# B198X.net
KiCad netlist of a schematic drawn in EAGLE
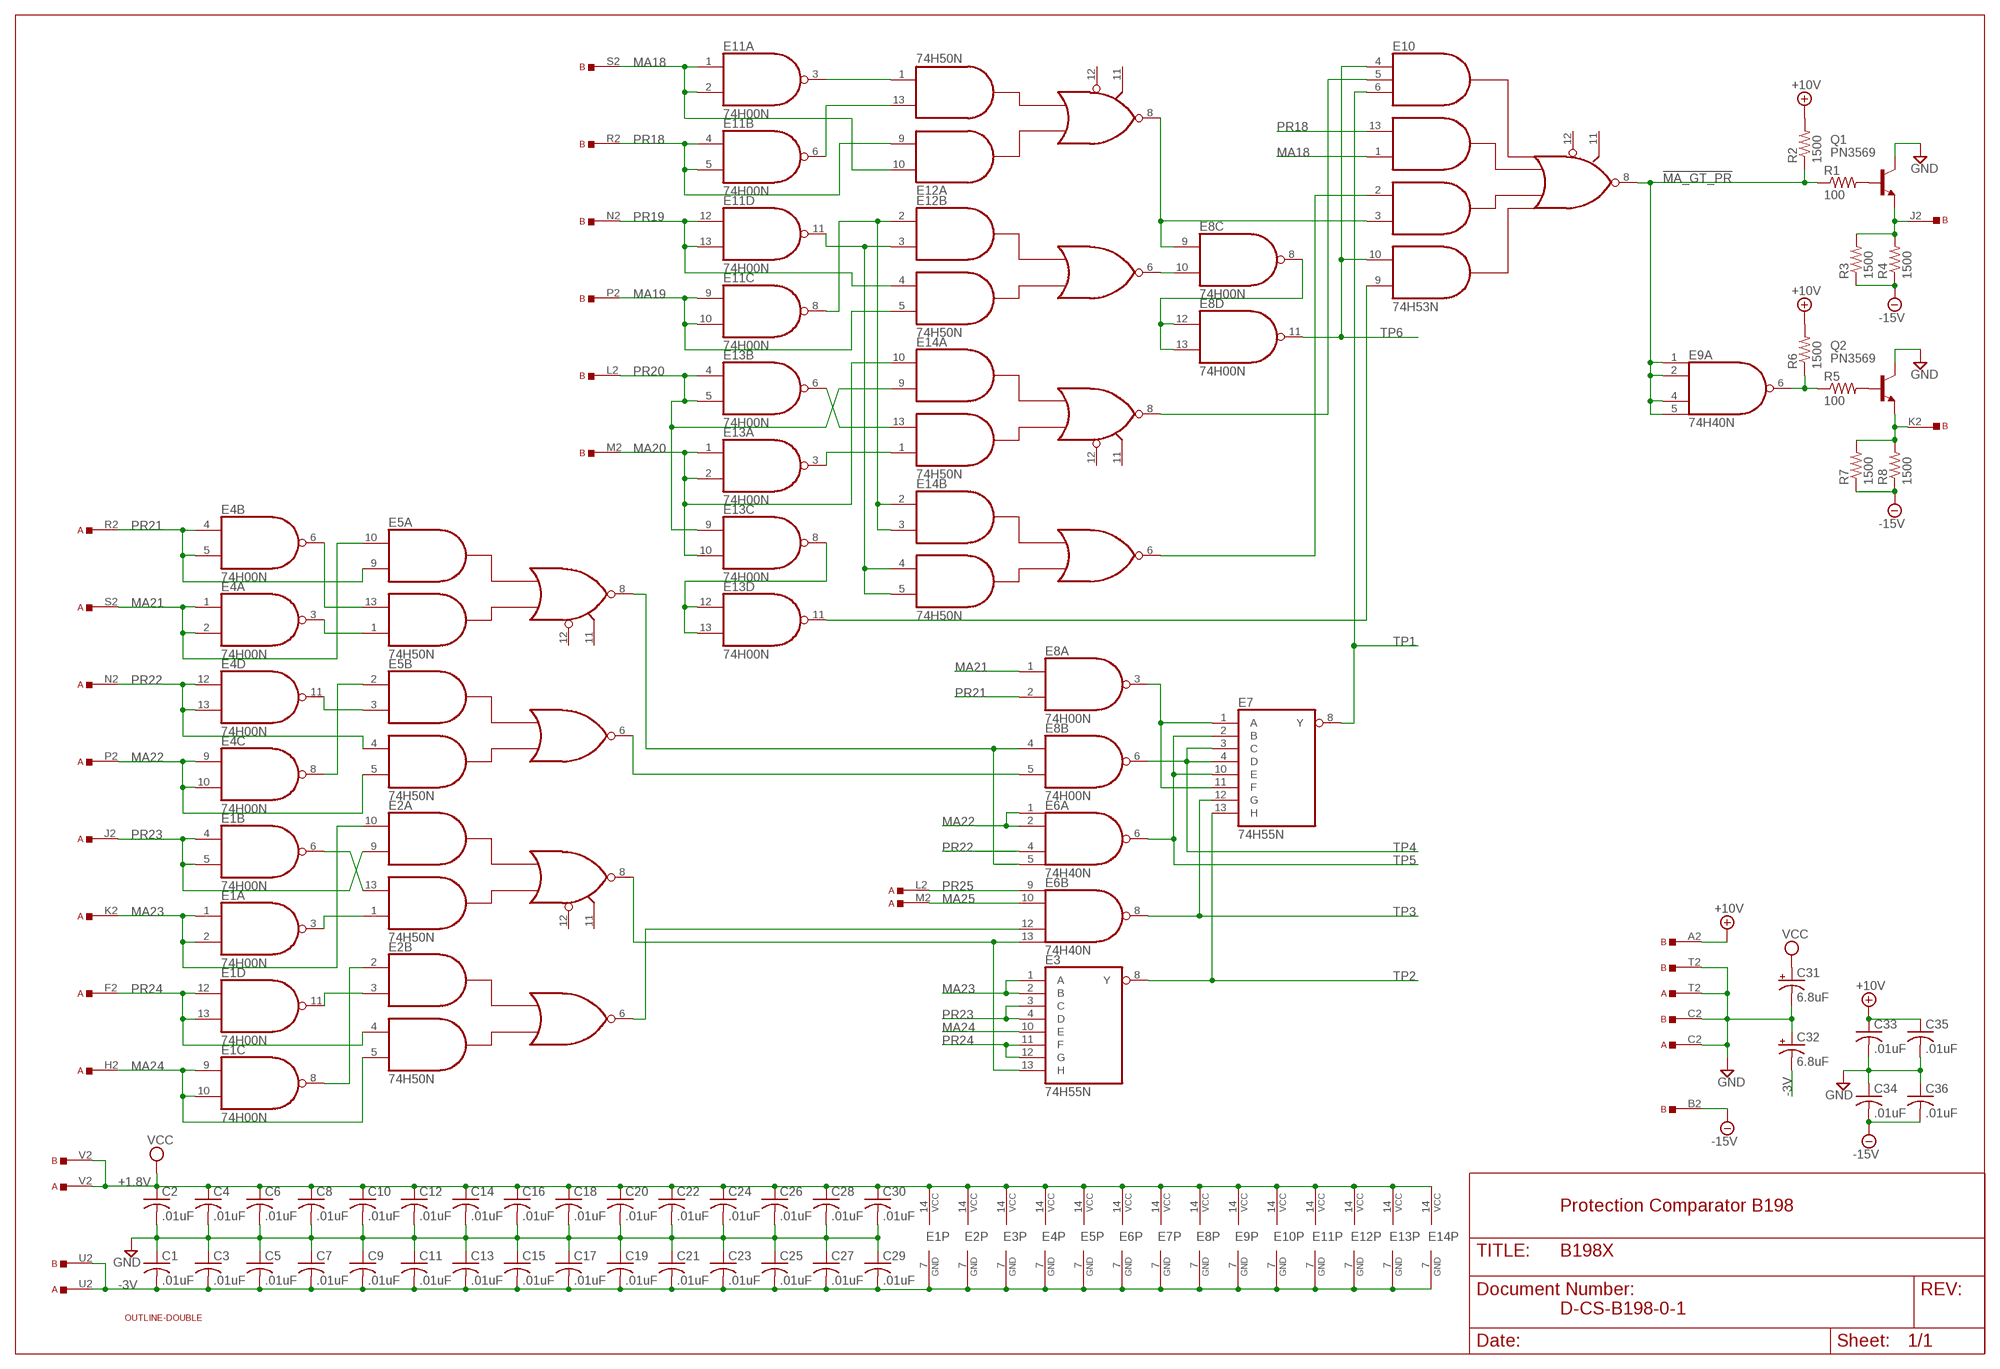
[diagram p0: schematic, sheet 1]

(export (version "E")
  (design (tool "Eeschema 10.0.6"))
  (components
    (comp (ref "A")
      (value "SS-TOP")
      (footprint "eagle-import:EDGE-CON1")
      (libsource (lib "eagle-import") (part "SS-TOP"))
    )
    (comp (ref "B")
      (value "SS-TOP")
      (footprint "eagle-import:EDGE-CON1")
      (libsource (lib "eagle-import") (part "SS-TOP"))
    )
    (comp (ref "C1")
      (value ".01uF")
      (footprint "eagle-import:C063-025X075")
      (libsource (lib "eagle-import") (part "C-US"))
    )
    (comp (ref "C2")
      (value ".01uF")
      (footprint "eagle-import:C063-025X075")
      (libsource (lib "eagle-import") (part "C-US"))
    )
    (comp (ref "C3")
      (value ".01uF")
      (footprint "eagle-import:C063-025X075")
      (libsource (lib "eagle-import") (part "C-US"))
    )
    (comp (ref "C4")
      (value ".01uF")
      (footprint "eagle-import:C063-025X075")
      (libsource (lib "eagle-import") (part "C-US"))
    )
    (comp (ref "C5")
      (value ".01uF")
      (footprint "eagle-import:C063-025X075")
      (libsource (lib "eagle-import") (part "C-US"))
    )
    (comp (ref "C6")
      (value ".01uF")
      (footprint "eagle-import:C063-025X075")
      (libsource (lib "eagle-import") (part "C-US"))
    )
    (comp (ref "C7")
      (value ".01uF")
      (footprint "eagle-import:C063-025X075")
      (libsource (lib "eagle-import") (part "C-US"))
    )
    (comp (ref "C8")
      (value ".01uF")
      (footprint "eagle-import:C063-025X075")
      (libsource (lib "eagle-import") (part "C-US"))
    )
    (comp (ref "C9")
      (value ".01uF")
      (footprint "eagle-import:C063-025X075")
      (libsource (lib "eagle-import") (part "C-US"))
    )
    (comp (ref "C10")
      (value ".01uF")
      (footprint "eagle-import:C063-025X075")
      (libsource (lib "eagle-import") (part "C-US"))
    )
    (comp (ref "C11")
      (value ".01uF")
      (footprint "eagle-import:C063-025X075")
      (libsource (lib "eagle-import") (part "C-US"))
    )
    (comp (ref "C12")
      (value ".01uF")
      (footprint "eagle-import:C063-025X075")
      (libsource (lib "eagle-import") (part "C-US"))
    )
    (comp (ref "C13")
      (value ".01uF")
      (footprint "eagle-import:C063-025X075")
      (libsource (lib "eagle-import") (part "C-US"))
    )
    (comp (ref "C14")
      (value ".01uF")
      (footprint "eagle-import:C063-025X075")
      (libsource (lib "eagle-import") (part "C-US"))
    )
    (comp (ref "C15")
      (value ".01uF")
      (footprint "eagle-import:C063-025X075")
      (libsource (lib "eagle-import") (part "C-US"))
    )
    (comp (ref "C16")
      (value ".01uF")
      (footprint "eagle-import:C063-025X075")
      (libsource (lib "eagle-import") (part "C-US"))
    )
    (comp (ref "C17")
      (value ".01uF")
      (footprint "eagle-import:C063-025X075")
      (libsource (lib "eagle-import") (part "C-US"))
    )
    (comp (ref "C18")
      (value ".01uF")
      (footprint "eagle-import:C063-025X075")
      (libsource (lib "eagle-import") (part "C-US"))
    )
    (comp (ref "C19")
      (value ".01uF")
      (footprint "eagle-import:C063-025X075")
      (libsource (lib "eagle-import") (part "C-US"))
    )
    (comp (ref "C20")
      (value ".01uF")
      (footprint "eagle-import:C063-025X075")
      (libsource (lib "eagle-import") (part "C-US"))
    )
    (comp (ref "C21")
      (value ".01uF")
      (footprint "eagle-import:C063-025X075")
      (libsource (lib "eagle-import") (part "C-US"))
    )
    (comp (ref "C22")
      (value ".01uF")
      (footprint "eagle-import:C063-025X075")
      (libsource (lib "eagle-import") (part "C-US"))
    )
    (comp (ref "C23")
      (value ".01uF")
      (footprint "eagle-import:C063-025X075")
      (libsource (lib "eagle-import") (part "C-US"))
    )
    (comp (ref "C24")
      (value ".01uF")
      (footprint "eagle-import:C063-025X075")
      (libsource (lib "eagle-import") (part "C-US"))
    )
    (comp (ref "C25")
      (value ".01uF")
      (footprint "eagle-import:C063-025X075")
      (libsource (lib "eagle-import") (part "C-US"))
    )
    (comp (ref "C26")
      (value ".01uF")
      (footprint "eagle-import:C063-025X075")
      (libsource (lib "eagle-import") (part "C-US"))
    )
    (comp (ref "C27")
      (value ".01uF")
      (footprint "eagle-import:C063-025X075")
      (libsource (lib "eagle-import") (part "C-US"))
    )
    (comp (ref "C28")
      (value ".01uF")
      (footprint "eagle-import:C063-025X075")
      (libsource (lib "eagle-import") (part "C-US"))
    )
    (comp (ref "C29")
      (value ".01uF")
      (footprint "eagle-import:C063-025X075")
      (libsource (lib "eagle-import") (part "C-US"))
    )
    (comp (ref "C30")
      (value ".01uF")
      (footprint "eagle-import:C063-025X075")
      (libsource (lib "eagle-import") (part "C-US"))
    )
    (comp (ref "C31")
      (value "6.8uF")
      (footprint "eagle-import:E15-5")
      (libsource (lib "eagle-import") (part "CPOL-USE15-5AXIAL"))
    )
    (comp (ref "C32")
      (value "6.8uF")
      (footprint "eagle-import:E15-5")
      (libsource (lib "eagle-import") (part "CPOL-USE15-5AXIAL"))
    )
    (comp (ref "C33")
      (value ".01uF")
      (footprint "eagle-import:C063-025X075")
      (libsource (lib "eagle-import") (part "C-US"))
    )
    (comp (ref "C34")
      (value ".01uF")
      (footprint "eagle-import:C063-025X075")
      (libsource (lib "eagle-import") (part "C-US"))
    )
    (comp (ref "C35")
      (value ".01uF")
      (footprint "eagle-import:C063-025X075")
      (libsource (lib "eagle-import") (part "C-US"))
    )
    (comp (ref "C36")
      (value ".01uF")
      (footprint "eagle-import:C063-025X075")
      (libsource (lib "eagle-import") (part "C-US"))
    )
    (comp (ref "E1")
      (value "74H00N")
      (footprint "eagle-import:DIL14")
      (libsource (lib "eagle-import") (part "7400NS"))
    )
    (comp (ref "E2")
      (value "74H50N")
      (footprint "eagle-import:DIL14")
      (libsource (lib "eagle-import") (part "7450N"))
    )
    (comp (ref "E3")
      (value "74H55N")
      (footprint "eagle-import:DIL14")
      (libsource (lib "eagle-import") (part "7455NLS"))
    )
    (comp (ref "E4")
      (value "74H00N")
      (footprint "eagle-import:DIL14")
      (libsource (lib "eagle-import") (part "7400NS"))
    )
    (comp (ref "E5")
      (value "74H50N")
      (footprint "eagle-import:DIL14")
      (libsource (lib "eagle-import") (part "7450N"))
    )
    (comp (ref "E6")
      (value "74H40N")
      (footprint "eagle-import:DIL14")
      (libsource (lib "eagle-import") (part "7440N"))
    )
    (comp (ref "E7")
      (value "74H55N")
      (footprint "eagle-import:DIL14")
      (libsource (lib "eagle-import") (part "7455NLS"))
    )
    (comp (ref "E8")
      (value "74H00N")
      (footprint "eagle-import:DIL14")
      (libsource (lib "eagle-import") (part "7400NS"))
    )
    (comp (ref "E9")
      (value "74H40N")
      (footprint "eagle-import:DIL14")
      (libsource (lib "eagle-import") (part "7440N"))
    )
    (comp (ref "E10")
      (value "74H53N")
      (footprint "eagle-import:DIL14")
      (libsource (lib "eagle-import") (part "74H53N"))
    )
    (comp (ref "E11")
      (value "74H00N")
      (footprint "eagle-import:DIL14")
      (libsource (lib "eagle-import") (part "7400NS"))
    )
    (comp (ref "E12")
      (value "74H50N")
      (footprint "eagle-import:DIL14")
      (libsource (lib "eagle-import") (part "7450N"))
    )
    (comp (ref "E13")
      (value "74H00N")
      (footprint "eagle-import:DIL14")
      (libsource (lib "eagle-import") (part "7400NS"))
    )
    (comp (ref "E14")
      (value "74H50N")
      (footprint "eagle-import:DIL14")
      (libsource (lib "eagle-import") (part "7450N"))
    )
    (comp (ref "Q1")
      (value "PN3569")
      (footprint "eagle-import:TO5")
      (libsource (lib "eagle-import") (part "-NPN-TO5"))
    )
    (comp (ref "Q2")
      (value "PN3569")
      (footprint "eagle-import:TO5")
      (libsource (lib "eagle-import") (part "-NPN-TO5"))
    )
    (comp (ref "R1")
      (value "100")
      (footprint "eagle-import:0207_10")
      (libsource (lib "eagle-import") (part "R-US_0207/10"))
    )
    (comp (ref "R2")
      (value "1500")
      (footprint "eagle-import:0207_10")
      (libsource (lib "eagle-import") (part "R-US_0207/10"))
    )
    (comp (ref "R3")
      (value "1500")
      (footprint "eagle-import:0207_10")
      (libsource (lib "eagle-import") (part "R-US_0207/10"))
    )
    (comp (ref "R4")
      (value "1500")
      (footprint "eagle-import:0207_10")
      (libsource (lib "eagle-import") (part "R-US_0207/10"))
    )
    (comp (ref "R5")
      (value "100")
      (footprint "eagle-import:0207_10")
      (libsource (lib "eagle-import") (part "R-US_0207/10"))
    )
    (comp (ref "R6")
      (value "1500")
      (footprint "eagle-import:0207_10")
      (libsource (lib "eagle-import") (part "R-US_0207/10"))
    )
    (comp (ref "R7")
      (value "1500")
      (footprint "eagle-import:0207_10")
      (libsource (lib "eagle-import") (part "R-US_0207/10"))
    )
    (comp (ref "R8")
      (value "1500")
      (footprint "eagle-import:0207_10")
      (libsource (lib "eagle-import") (part "R-US_0207/10"))
    )
    (comp (ref "U$1")
      (value "OUTLINE-DOUBLE")
      (footprint "eagle-import:DOUBLE")
      (libsource (lib "eagle-import") (part "OUTLINE-DOUBLE"))
    )
  )
  (nets
    (net (code "1") (name "+10V") (class "Default")
      (node (ref "B") (pin "A2") (pinfunction "P_A2") (pintype "passive"))
      (node (ref "C33") (pin "1") (pinfunction "1_1") (pintype "passive"))
      (node (ref "C35") (pin "1") (pinfunction "1_1") (pintype "passive"))
      (node (ref "R2") (pin "2") (pinfunction "2_2") (pintype "passive"))
      (node (ref "R6") (pin "2") (pinfunction "2_2") (pintype "passive"))
    )
    (net (code "2") (name "-15V") (class "Default")
      (node (ref "B") (pin "B2") (pinfunction "P_B2") (pintype "passive"))
      (node (ref "C34") (pin "2") (pinfunction "2_2") (pintype "passive"))
      (node (ref "C36") (pin "2") (pinfunction "2_2") (pintype "passive"))
      (node (ref "R3") (pin "1") (pinfunction "1_1") (pintype "passive"))
      (node (ref "R4") (pin "1") (pinfunction "1_1") (pintype "passive"))
      (node (ref "R7") (pin "1") (pinfunction "1_1") (pintype "passive"))
      (node (ref "R8") (pin "1") (pinfunction "1_1") (pintype "passive"))
    )
    (net (code "3") (name "/-3V") (class "Default")
      (node (ref "A") (pin "U2") (pinfunction "P_U2") (pintype "passive"))
      (node (ref "B") (pin "U2") (pinfunction "P_U2") (pintype "passive"))
      (node (ref "C1") (pin "2") (pinfunction "2_2") (pintype "passive"))
      (node (ref "C11") (pin "2") (pinfunction "2_2") (pintype "passive"))
      (node (ref "C13") (pin "2") (pinfunction "2_2") (pintype "passive"))
      (node (ref "C15") (pin "2") (pinfunction "2_2") (pintype "passive"))
      (node (ref "C17") (pin "2") (pinfunction "2_2") (pintype "passive"))
      (node (ref "C19") (pin "2") (pinfunction "2_2") (pintype "passive"))
      (node (ref "C21") (pin "2") (pinfunction "2_2") (pintype "passive"))
      (node (ref "C23") (pin "2") (pinfunction "2_2") (pintype "passive"))
      (node (ref "C25") (pin "2") (pinfunction "2_2") (pintype "passive"))
      (node (ref "C27") (pin "2") (pinfunction "2_2") (pintype "passive"))
      (node (ref "C29") (pin "2") (pinfunction "2_2") (pintype "passive"))
      (node (ref "C3") (pin "2") (pinfunction "2_2") (pintype "passive"))
      (node (ref "C32") (pin "-") (pinfunction "-_-") (pintype "passive"))
      (node (ref "C5") (pin "2") (pinfunction "2_2") (pintype "passive"))
      (node (ref "C7") (pin "2") (pinfunction "2_2") (pintype "passive"))
      (node (ref "C9") (pin "2") (pinfunction "2_2") (pintype "passive"))
      (node (ref "E1") (pin "7") (pinfunction "GND_7") (pintype "power_in"))
      (node (ref "E10") (pin "7") (pinfunction "GND_7") (pintype "power_in"))
      (node (ref "E11") (pin "7") (pinfunction "GND_7") (pintype "power_in"))
      (node (ref "E12") (pin "7") (pinfunction "GND_7") (pintype "power_in"))
      (node (ref "E13") (pin "7") (pinfunction "GND_7") (pintype "power_in"))
      (node (ref "E14") (pin "7") (pinfunction "GND_7") (pintype "power_in"))
      (node (ref "E2") (pin "7") (pinfunction "GND_7") (pintype "power_in"))
      (node (ref "E3") (pin "7") (pinfunction "GND_7") (pintype "power_in"))
      (node (ref "E4") (pin "7") (pinfunction "GND_7") (pintype "power_in"))
      (node (ref "E5") (pin "7") (pinfunction "GND_7") (pintype "power_in"))
      (node (ref "E6") (pin "7") (pinfunction "GND_7") (pintype "power_in"))
      (node (ref "E7") (pin "7") (pinfunction "GND_7") (pintype "power_in"))
      (node (ref "E8") (pin "7") (pinfunction "GND_7") (pintype "power_in"))
      (node (ref "E9") (pin "7") (pinfunction "GND_7") (pintype "power_in"))
    )
    (net (code "4") (name "/MA18") (class "Default")
      (node (ref "B") (pin "S2") (pinfunction "P_S2") (pintype "passive"))
      (node (ref "E10") (pin "1") (pinfunction "I4_1") (pintype "input"))
      (node (ref "E11") (pin "1") (pinfunction "I0_1") (pintype "input"))
      (node (ref "E11") (pin "2") (pinfunction "I1_2") (pintype "input"))
      (node (ref "E12") (pin "10") (pinfunction "I1_10") (pintype "input"))
    )
    (net (code "5") (name "/MA19") (class "Default")
      (node (ref "B") (pin "P2") (pinfunction "P_P2") (pintype "passive"))
      (node (ref "E11") (pin "10") (pinfunction "I1_10") (pintype "input"))
      (node (ref "E11") (pin "9") (pinfunction "I0_9") (pintype "input"))
      (node (ref "E12") (pin "5") (pinfunction "I4_5") (pintype "input"))
    )
    (net (code "6") (name "/MA20") (class "Default")
      (node (ref "B") (pin "M2") (pinfunction "P_M2") (pintype "passive"))
      (node (ref "E13") (pin "1") (pinfunction "I0_1") (pintype "input"))
      (node (ref "E13") (pin "10") (pinfunction "I1_10") (pintype "input"))
      (node (ref "E13") (pin "2") (pinfunction "I1_2") (pintype "input"))
      (node (ref "E14") (pin "10") (pinfunction "I1_10") (pintype "input"))
    )
    (net (code "7") (name "/MA21") (class "Default")
      (node (ref "A") (pin "S2") (pinfunction "P_S2") (pintype "passive"))
      (node (ref "E4") (pin "1") (pinfunction "I0_1") (pintype "input"))
      (node (ref "E4") (pin "2") (pinfunction "I1_2") (pintype "input"))
      (node (ref "E5") (pin "10") (pinfunction "I1_10") (pintype "input"))
      (node (ref "E8") (pin "1") (pinfunction "I0_1") (pintype "input"))
    )
    (net (code "8") (name "/MA22") (class "Default")
      (node (ref "A") (pin "P2") (pinfunction "P_P2") (pintype "passive"))
      (node (ref "E4") (pin "10") (pinfunction "I1_10") (pintype "input"))
      (node (ref "E4") (pin "9") (pinfunction "I0_9") (pintype "input"))
      (node (ref "E5") (pin "5") (pinfunction "I4_5") (pintype "input"))
      (node (ref "E6") (pin "1") (pinfunction "I0_1") (pintype "input"))
      (node (ref "E6") (pin "2") (pinfunction "I1_2") (pintype "input"))
    )
    (net (code "9") (name "/MA23") (class "Default")
      (node (ref "A") (pin "K2") (pinfunction "P_K2") (pintype "passive"))
      (node (ref "E1") (pin "1") (pinfunction "I0_1") (pintype "input"))
      (node (ref "E1") (pin "2") (pinfunction "I1_2") (pintype "input"))
      (node (ref "E2") (pin "10") (pinfunction "I1_10") (pintype "input"))
      (node (ref "E3") (pin "1") (pinfunction "A_1") (pintype "input"))
      (node (ref "E3") (pin "2") (pinfunction "B_2") (pintype "input"))
    )
    (net (code "10") (name "/MA24") (class "Default")
      (node (ref "A") (pin "H2") (pinfunction "P_H2") (pintype "passive"))
      (node (ref "E1") (pin "10") (pinfunction "I1_10") (pintype "input"))
      (node (ref "E1") (pin "9") (pinfunction "I0_9") (pintype "input"))
      (node (ref "E2") (pin "5") (pinfunction "I4_5") (pintype "input"))
      (node (ref "E3") (pin "10") (pinfunction "E_10") (pintype "input"))
    )
    (net (code "11") (name "/MA25") (class "Default")
      (node (ref "A") (pin "M2") (pinfunction "P_M2") (pintype "passive"))
      (node (ref "E6") (pin "10") (pinfunction "I1_10") (pintype "input"))
    )
    (net (code "12") (name "/PR18") (class "Default")
      (node (ref "B") (pin "R2") (pinfunction "P_R2") (pintype "passive"))
      (node (ref "E10") (pin "13") (pinfunction "I3_13") (pintype "input"))
      (node (ref "E11") (pin "4") (pinfunction "I0_4") (pintype "input"))
      (node (ref "E11") (pin "5") (pinfunction "I1_5") (pintype "input"))
      (node (ref "E12") (pin "9") (pinfunction "I2_9") (pintype "input"))
    )
    (net (code "13") (name "/PR19") (class "Default")
      (node (ref "B") (pin "N2") (pinfunction "P_N2") (pintype "passive"))
      (node (ref "E11") (pin "12") (pinfunction "I0_12") (pintype "input"))
      (node (ref "E11") (pin "13") (pinfunction "I1_13") (pintype "input"))
      (node (ref "E12") (pin "4") (pinfunction "I3_4") (pintype "input"))
    )
    (net (code "14") (name "/PR20") (class "Default")
      (node (ref "B") (pin "L2") (pinfunction "P_L2") (pintype "passive"))
      (node (ref "E13") (pin "4") (pinfunction "I0_4") (pintype "input"))
      (node (ref "E13") (pin "5") (pinfunction "I1_5") (pintype "input"))
      (node (ref "E13") (pin "9") (pinfunction "I0_9") (pintype "input"))
      (node (ref "E14") (pin "9") (pinfunction "I2_9") (pintype "input"))
    )
    (net (code "15") (name "/PR21") (class "Default")
      (node (ref "A") (pin "R2") (pinfunction "P_R2") (pintype "passive"))
      (node (ref "E4") (pin "4") (pinfunction "I0_4") (pintype "input"))
      (node (ref "E4") (pin "5") (pinfunction "I1_5") (pintype "input"))
      (node (ref "E5") (pin "9") (pinfunction "I2_9") (pintype "input"))
      (node (ref "E8") (pin "2") (pinfunction "I1_2") (pintype "input"))
    )
    (net (code "16") (name "/PR22") (class "Default")
      (node (ref "A") (pin "N2") (pinfunction "P_N2") (pintype "passive"))
      (node (ref "E4") (pin "12") (pinfunction "I0_12") (pintype "input"))
      (node (ref "E4") (pin "13") (pinfunction "I1_13") (pintype "input"))
      (node (ref "E5") (pin "4") (pinfunction "I3_4") (pintype "input"))
      (node (ref "E6") (pin "4") (pinfunction "I2_4") (pintype "input"))
    )
    (net (code "17") (name "/PR23") (class "Default")
      (node (ref "A") (pin "J2") (pinfunction "P_J2") (pintype "passive"))
      (node (ref "E1") (pin "4") (pinfunction "I0_4") (pintype "input"))
      (node (ref "E1") (pin "5") (pinfunction "I1_5") (pintype "input"))
      (node (ref "E2") (pin "9") (pinfunction "I2_9") (pintype "input"))
      (node (ref "E3") (pin "3") (pinfunction "C_3") (pintype "input"))
      (node (ref "E3") (pin "4") (pinfunction "D_4") (pintype "input"))
    )
    (net (code "18") (name "/PR24") (class "Default")
      (node (ref "A") (pin "F2") (pinfunction "P_F2") (pintype "passive"))
      (node (ref "E1") (pin "12") (pinfunction "I0_12") (pintype "input"))
      (node (ref "E1") (pin "13") (pinfunction "I1_13") (pintype "input"))
      (node (ref "E2") (pin "4") (pinfunction "I3_4") (pintype "input"))
      (node (ref "E3") (pin "11") (pinfunction "F_11") (pintype "input"))
      (node (ref "E3") (pin "12") (pinfunction "G_12") (pintype "input"))
    )
    (net (code "19") (name "/PR25") (class "Default")
      (node (ref "A") (pin "L2") (pinfunction "P_L2") (pintype "passive"))
      (node (ref "E6") (pin "9") (pinfunction "I0_9") (pintype "input"))
    )
    (net (code "20") (name "/TP1") (class "Default")
      (node (ref "E10") (pin "6") (pinfunction "I2_6") (pintype "input"))
      (node (ref "E7") (pin "8") (pinfunction "Y_8") (pintype "output"))
    )
    (net (code "21") (name "/TP2") (class "Default")
      (node (ref "E3") (pin "8") (pinfunction "Y_8") (pintype "output"))
      (node (ref "E7") (pin "13") (pinfunction "H_13") (pintype "input"))
    )
    (net (code "22") (name "/TP3") (class "Default")
      (node (ref "E6") (pin "8") (pinfunction "O_8") (pintype "output"))
      (node (ref "E7") (pin "12") (pinfunction "G_12") (pintype "input"))
    )
    (net (code "23") (name "/TP4") (class "Default")
      (node (ref "E7") (pin "3") (pinfunction "C_3") (pintype "input"))
      (node (ref "E7") (pin "4") (pinfunction "D_4") (pintype "input"))
      (node (ref "E8") (pin "6") (pinfunction "O_6") (pintype "output"))
    )
    (net (code "24") (name "/TP5") (class "Default")
      (node (ref "E6") (pin "6") (pinfunction "O_6") (pintype "output"))
      (node (ref "E7") (pin "10") (pinfunction "E_10") (pintype "input"))
      (node (ref "E7") (pin "2") (pinfunction "B_2") (pintype "input"))
    )
    (net (code "25") (name "/TP6") (class "Default")
      (node (ref "E10") (pin "10") (pinfunction "I7_10") (pintype "input"))
      (node (ref "E10") (pin "4") (pinfunction "I1_4") (pintype "input"))
      (node (ref "E8") (pin "11") (pinfunction "O_11") (pintype "output"))
    )
    (net (code "26") (name "/~{MA_GT_PR}") (class "Default")
      (node (ref "E10") (pin "8") (pinfunction "O_8") (pintype "output"))
      (node (ref "E9") (pin "1") (pinfunction "I0_1") (pintype "input"))
      (node (ref "E9") (pin "2") (pinfunction "I1_2") (pintype "input"))
      (node (ref "E9") (pin "4") (pinfunction "I2_4") (pintype "input"))
      (node (ref "E9") (pin "5") (pinfunction "I3_5") (pintype "input"))
      (node (ref "R1") (pin "1") (pinfunction "1_1") (pintype "passive"))
      (node (ref "R2") (pin "1") (pinfunction "1_1") (pintype "passive"))
    )
    (net (code "27") (name "GND") (class "Default")
      (node (ref "A") (pin "C2") (pinfunction "P_C2") (pintype "passive"))
      (node (ref "A") (pin "T2") (pinfunction "P_T2") (pintype "passive"))
      (node (ref "B") (pin "C2") (pinfunction "P_C2") (pintype "passive"))
      (node (ref "B") (pin "T2") (pinfunction "P_T2") (pintype "passive"))
      (node (ref "C1") (pin "1") (pinfunction "1_1") (pintype "passive"))
      (node (ref "C10") (pin "2") (pinfunction "2_2") (pintype "passive"))
      (node (ref "C11") (pin "1") (pinfunction "1_1") (pintype "passive"))
      (node (ref "C12") (pin "2") (pinfunction "2_2") (pintype "passive"))
      (node (ref "C13") (pin "1") (pinfunction "1_1") (pintype "passive"))
      (node (ref "C14") (pin "2") (pinfunction "2_2") (pintype "passive"))
      (node (ref "C15") (pin "1") (pinfunction "1_1") (pintype "passive"))
      (node (ref "C16") (pin "2") (pinfunction "2_2") (pintype "passive"))
      (node (ref "C17") (pin "1") (pinfunction "1_1") (pintype "passive"))
      (node (ref "C18") (pin "2") (pinfunction "2_2") (pintype "passive"))
      (node (ref "C19") (pin "1") (pinfunction "1_1") (pintype "passive"))
      (node (ref "C2") (pin "2") (pinfunction "2_2") (pintype "passive"))
      (node (ref "C20") (pin "2") (pinfunction "2_2") (pintype "passive"))
      (node (ref "C21") (pin "1") (pinfunction "1_1") (pintype "passive"))
      (node (ref "C22") (pin "2") (pinfunction "2_2") (pintype "passive"))
      (node (ref "C23") (pin "1") (pinfunction "1_1") (pintype "passive"))
      (node (ref "C24") (pin "2") (pinfunction "2_2") (pintype "passive"))
      (node (ref "C25") (pin "1") (pinfunction "1_1") (pintype "passive"))
      (node (ref "C26") (pin "2") (pinfunction "2_2") (pintype "passive"))
      (node (ref "C27") (pin "1") (pinfunction "1_1") (pintype "passive"))
      (node (ref "C28") (pin "2") (pinfunction "2_2") (pintype "passive"))
      (node (ref "C29") (pin "1") (pinfunction "1_1") (pintype "passive"))
      (node (ref "C3") (pin "1") (pinfunction "1_1") (pintype "passive"))
      (node (ref "C30") (pin "2") (pinfunction "2_2") (pintype "passive"))
      (node (ref "C31") (pin "-") (pinfunction "-_-") (pintype "passive"))
      (node (ref "C32") (pin "+") (pinfunction "+_+") (pintype "passive"))
      (node (ref "C33") (pin "2") (pinfunction "2_2") (pintype "passive"))
      (node (ref "C34") (pin "1") (pinfunction "1_1") (pintype "passive"))
      (node (ref "C35") (pin "2") (pinfunction "2_2") (pintype "passive"))
      (node (ref "C36") (pin "1") (pinfunction "1_1") (pintype "passive"))
      (node (ref "C4") (pin "2") (pinfunction "2_2") (pintype "passive"))
      (node (ref "C5") (pin "1") (pinfunction "1_1") (pintype "passive"))
      (node (ref "C6") (pin "2") (pinfunction "2_2") (pintype "passive"))
      (node (ref "C7") (pin "1") (pinfunction "1_1") (pintype "passive"))
      (node (ref "C8") (pin "2") (pinfunction "2_2") (pintype "passive"))
      (node (ref "C9") (pin "1") (pinfunction "1_1") (pintype "passive"))
      (node (ref "Q1") (pin "3") (pinfunction "C_3") (pintype "passive"))
      (node (ref "Q2") (pin "3") (pinfunction "C_3") (pintype "passive"))
    )
    (net (code "28") (name "Net-(BH-P)") (class "Default")
      (node (ref "B") (pin "J2") (pinfunction "P_J2") (pintype "passive"))
      (node (ref "Q1") (pin "1") (pinfunction "E_1") (pintype "passive"))
      (node (ref "R3") (pin "2") (pinfunction "2_2") (pintype "passive"))
      (node (ref "R4") (pin "2") (pinfunction "2_2") (pintype "passive"))
    )
    (net (code "29") (name "Net-(BI-P)") (class "Default")
      (node (ref "B") (pin "K2") (pinfunction "P_K2") (pintype "passive"))
      (node (ref "Q2") (pin "1") (pinfunction "E_1") (pintype "passive"))
      (node (ref "R7") (pin "2") (pinfunction "2_2") (pintype "passive"))
      (node (ref "R8") (pin "2") (pinfunction "2_2") (pintype "passive"))
    )
    (net (code "30") (name "Net-(E1A-O)") (class "Default")
      (node (ref "E1") (pin "3") (pinfunction "O_3") (pintype "output"))
      (node (ref "E2") (pin "1") (pinfunction "I4_1") (pintype "input"))
    )
    (net (code "31") (name "Net-(E1B-O)") (class "Default")
      (node (ref "E1") (pin "6") (pinfunction "O_6") (pintype "output"))
      (node (ref "E2") (pin "13") (pinfunction "I3_13") (pintype "input"))
    )
    (net (code "32") (name "Net-(E1C-O)") (class "Default")
      (node (ref "E1") (pin "8") (pinfunction "O_8") (pintype "output"))
      (node (ref "E2") (pin "2") (pinfunction "I1_2") (pintype "input"))
    )
    (net (code "33") (name "Net-(E1D-O)") (class "Default")
      (node (ref "E1") (pin "11") (pinfunction "O_11") (pintype "output"))
      (node (ref "E2") (pin "3") (pinfunction "I2_3") (pintype "input"))
    )
    (net (code "34") (name "Net-(E2A-O)") (class "Default")
      (node (ref "E2") (pin "8") (pinfunction "O_8") (pintype "output"))
      (node (ref "E3") (pin "13") (pinfunction "H_13") (pintype "input"))
      (node (ref "E6") (pin "13") (pinfunction "I3_13") (pintype "input"))
    )
    (net (code "35") (name "Net-(E2B-O)") (class "Default")
      (node (ref "E2") (pin "6") (pinfunction "O_6") (pintype "output"))
      (node (ref "E6") (pin "12") (pinfunction "I2_12") (pintype "input"))
    )
    (net (code "36") (name "Net-(E4A-O)") (class "Default")
      (node (ref "E4") (pin "3") (pinfunction "O_3") (pintype "output"))
      (node (ref "E5") (pin "1") (pinfunction "I4_1") (pintype "input"))
    )
    (net (code "37") (name "Net-(E4B-O)") (class "Default")
      (node (ref "E4") (pin "6") (pinfunction "O_6") (pintype "output"))
      (node (ref "E5") (pin "13") (pinfunction "I3_13") (pintype "input"))
    )
    (net (code "38") (name "Net-(E4C-O)") (class "Default")
      (node (ref "E4") (pin "8") (pinfunction "O_8") (pintype "output"))
      (node (ref "E5") (pin "2") (pinfunction "I1_2") (pintype "input"))
    )
    (net (code "39") (name "Net-(E4D-O)") (class "Default")
      (node (ref "E4") (pin "11") (pinfunction "O_11") (pintype "output"))
      (node (ref "E5") (pin "3") (pinfunction "I2_3") (pintype "input"))
    )
    (net (code "40") (name "Net-(E5A-O)") (class "Default")
      (node (ref "E5") (pin "8") (pinfunction "O_8") (pintype "output"))
      (node (ref "E6") (pin "5") (pinfunction "I3_5") (pintype "input"))
      (node (ref "E8") (pin "4") (pinfunction "I0_4") (pintype "input"))
    )
    (net (code "41") (name "Net-(E5B-O)") (class "Default")
      (node (ref "E5") (pin "6") (pinfunction "O_6") (pintype "output"))
      (node (ref "E8") (pin "5") (pinfunction "I1_5") (pintype "input"))
    )
    (net (code "42") (name "Net-(E7A-A)") (class "Default")
      (node (ref "E7") (pin "1") (pinfunction "A_1") (pintype "input"))
      (node (ref "E7") (pin "11") (pinfunction "F_11") (pintype "input"))
      (node (ref "E8") (pin "3") (pinfunction "O_3") (pintype "output"))
    )
    (net (code "43") (name "Net-(E8C-O)") (class "Default")
      (node (ref "E8") (pin "12") (pinfunction "I0_12") (pintype "input"))
      (node (ref "E8") (pin "13") (pinfunction "I1_13") (pintype "input"))
      (node (ref "E8") (pin "8") (pinfunction "O_8") (pintype "output"))
    )
    (net (code "44") (name "Net-(E9C-O)") (class "Default")
      (node (ref "E9") (pin "6") (pinfunction "O_6") (pintype "output"))
      (node (ref "R5") (pin "1") (pinfunction "1_1") (pintype "passive"))
      (node (ref "R6") (pin "1") (pinfunction "1_1") (pintype "passive"))
    )
    (net (code "45") (name "Net-(E10A-I5)") (class "Default")
      (node (ref "E10") (pin "2") (pinfunction "I5_2") (pintype "input"))
      (node (ref "E14") (pin "6") (pinfunction "O_6") (pintype "output"))
    )
    (net (code "46") (name "Net-(E10A-I6)") (class "Default")
      (node (ref "E10") (pin "3") (pinfunction "I6_3") (pintype "input"))
      (node (ref "E12") (pin "8") (pinfunction "O_8") (pintype "output"))
      (node (ref "E8") (pin "9") (pinfunction "I0_9") (pintype "input"))
    )
    (net (code "47") (name "Net-(E10A-I8)") (class "Default")
      (node (ref "E10") (pin "9") (pinfunction "I8_9") (pintype "input"))
      (node (ref "E13") (pin "11") (pinfunction "O_11") (pintype "output"))
    )
    (net (code "48") (name "Net-(E10A-I11)") (class "Default")
      (node (ref "E10") (pin "5") (pinfunction "I11_5") (pintype "input"))
      (node (ref "E14") (pin "8") (pinfunction "O_8") (pintype "output"))
    )
    (net (code "49") (name "Net-(E11A-O)") (class "Default")
      (node (ref "E11") (pin "3") (pinfunction "O_3") (pintype "output"))
      (node (ref "E12") (pin "1") (pinfunction "I4_1") (pintype "input"))
    )
    (net (code "50") (name "Net-(E11B-O)") (class "Default")
      (node (ref "E11") (pin "6") (pinfunction "O_6") (pintype "output"))
      (node (ref "E12") (pin "13") (pinfunction "I3_13") (pintype "input"))
    )
    (net (code "51") (name "Net-(E11C-O)") (class "Default")
      (node (ref "E11") (pin "8") (pinfunction "O_8") (pintype "output"))
      (node (ref "E12") (pin "2") (pinfunction "I1_2") (pintype "input"))
      (node (ref "E14") (pin "2") (pinfunction "I1_2") (pintype "input"))
      (node (ref "E14") (pin "3") (pinfunction "I2_3") (pintype "input"))
    )
    (net (code "52") (name "Net-(E11D-O)") (class "Default")
      (node (ref "E11") (pin "11") (pinfunction "O_11") (pintype "output"))
      (node (ref "E12") (pin "3") (pinfunction "I2_3") (pintype "input"))
      (node (ref "E14") (pin "4") (pinfunction "I3_4") (pintype "input"))
      (node (ref "E14") (pin "5") (pinfunction "I4_5") (pintype "input"))
    )
    (net (code "53") (name "Net-(E12B-O)") (class "Default")
      (node (ref "E12") (pin "6") (pinfunction "O_6") (pintype "output"))
      (node (ref "E8") (pin "10") (pinfunction "I1_10") (pintype "input"))
    )
    (net (code "54") (name "Net-(E13A-O)") (class "Default")
      (node (ref "E13") (pin "3") (pinfunction "O_3") (pintype "output"))
      (node (ref "E14") (pin "1") (pinfunction "I4_1") (pintype "input"))
    )
    (net (code "55") (name "Net-(E13B-O)") (class "Default")
      (node (ref "E13") (pin "6") (pinfunction "O_6") (pintype "output"))
      (node (ref "E14") (pin "13") (pinfunction "I3_13") (pintype "input"))
    )
    (net (code "56") (name "Net-(E13C-O)") (class "Default")
      (node (ref "E13") (pin "12") (pinfunction "I0_12") (pintype "input"))
      (node (ref "E13") (pin "13") (pinfunction "I1_13") (pintype "input"))
      (node (ref "E13") (pin "8") (pinfunction "O_8") (pintype "output"))
    )
    (net (code "57") (name "Net-(Q1-B)") (class "Default")
      (node (ref "Q1") (pin "2") (pinfunction "B_2") (pintype "passive"))
      (node (ref "R1") (pin "2") (pinfunction "2_2") (pintype "passive"))
    )
    (net (code "58") (name "Net-(Q2-B)") (class "Default")
      (node (ref "Q2") (pin "2") (pinfunction "B_2") (pintype "passive"))
      (node (ref "R5") (pin "2") (pinfunction "2_2") (pintype "passive"))
    )
    (net (code "59") (name "VCC") (class "Default")
      (node (ref "A") (pin "V2") (pinfunction "P_V2") (pintype "passive"))
      (node (ref "B") (pin "V2") (pinfunction "P_V2") (pintype "passive"))
      (node (ref "C10") (pin "1") (pinfunction "1_1") (pintype "passive"))
      (node (ref "C12") (pin "1") (pinfunction "1_1") (pintype "passive"))
      (node (ref "C14") (pin "1") (pinfunction "1_1") (pintype "passive"))
      (node (ref "C16") (pin "1") (pinfunction "1_1") (pintype "passive"))
      (node (ref "C18") (pin "1") (pinfunction "1_1") (pintype "passive"))
      (node (ref "C2") (pin "1") (pinfunction "1_1") (pintype "passive"))
      (node (ref "C20") (pin "1") (pinfunction "1_1") (pintype "passive"))
      (node (ref "C22") (pin "1") (pinfunction "1_1") (pintype "passive"))
      (node (ref "C24") (pin "1") (pinfunction "1_1") (pintype "passive"))
      (node (ref "C26") (pin "1") (pinfunction "1_1") (pintype "passive"))
      (node (ref "C28") (pin "1") (pinfunction "1_1") (pintype "passive"))
      (node (ref "C30") (pin "1") (pinfunction "1_1") (pintype "passive"))
      (node (ref "C31") (pin "+") (pinfunction "+_+") (pintype "passive"))
      (node (ref "C4") (pin "1") (pinfunction "1_1") (pintype "passive"))
      (node (ref "C6") (pin "1") (pinfunction "1_1") (pintype "passive"))
      (node (ref "C8") (pin "1") (pinfunction "1_1") (pintype "passive"))
      (node (ref "E1") (pin "14") (pinfunction "VCC_14") (pintype "power_in"))
      (node (ref "E10") (pin "14") (pinfunction "VCC_14") (pintype "power_in"))
      (node (ref "E11") (pin "14") (pinfunction "VCC_14") (pintype "power_in"))
      (node (ref "E12") (pin "14") (pinfunction "VCC_14") (pintype "power_in"))
      (node (ref "E13") (pin "14") (pinfunction "VCC_14") (pintype "power_in"))
      (node (ref "E14") (pin "14") (pinfunction "VCC_14") (pintype "power_in"))
      (node (ref "E2") (pin "14") (pinfunction "VCC_14") (pintype "power_in"))
      (node (ref "E3") (pin "14") (pinfunction "VCC_14") (pintype "power_in"))
      (node (ref "E4") (pin "14") (pinfunction "VCC_14") (pintype "power_in"))
      (node (ref "E5") (pin "14") (pinfunction "VCC_14") (pintype "power_in"))
      (node (ref "E6") (pin "14") (pinfunction "VCC_14") (pintype "power_in"))
      (node (ref "E7") (pin "14") (pinfunction "VCC_14") (pintype "power_in"))
      (node (ref "E8") (pin "14") (pinfunction "VCC_14") (pintype "power_in"))
      (node (ref "E9") (pin "14") (pinfunction "VCC_14") (pintype "power_in"))
    )
    (net (code "60") (name "unconnected-(E2A-I5-Pad12)") (class "Default")
      (node (ref "E2") (pin "12") (pinfunction "I5_12") (pintype "passive"))
    )
    (net (code "61") (name "unconnected-(E2A-I6-Pad11)") (class "Default")
      (node (ref "E2") (pin "11") (pinfunction "I6_11") (pintype "passive"))
    )
    (net (code "62") (name "unconnected-(E5A-I5-Pad12)") (class "Default")
      (node (ref "E5") (pin "12") (pinfunction "I5_12") (pintype "passive"))
    )
    (net (code "63") (name "unconnected-(E5A-I6-Pad11)") (class "Default")
      (node (ref "E5") (pin "11") (pinfunction "I6_11") (pintype "passive"))
    )
    (net (code "64") (name "unconnected-(E10A-I9-Pad12)") (class "Default")
      (node (ref "E10") (pin "12") (pinfunction "I9_12") (pintype "passive"))
    )
    (net (code "65") (name "unconnected-(E10A-I10-Pad11)") (class "Default")
      (node (ref "E10") (pin "11") (pinfunction "I10_11") (pintype "passive"))
    )
    (net (code "66") (name "unconnected-(E12A-I5-Pad12)") (class "Default")
      (node (ref "E12") (pin "12") (pinfunction "I5_12") (pintype "passive"))
    )
    (net (code "67") (name "unconnected-(E12A-I6-Pad11)") (class "Default")
      (node (ref "E12") (pin "11") (pinfunction "I6_11") (pintype "passive"))
    )
    (net (code "68") (name "unconnected-(E14A-I5-Pad12)") (class "Default")
      (node (ref "E14") (pin "12") (pinfunction "I5_12") (pintype "passive"))
    )
    (net (code "69") (name "unconnected-(E14A-I6-Pad11)") (class "Default")
      (node (ref "E14") (pin "11") (pinfunction "I6_11") (pintype "passive"))
    )
  )
)
